# 8-Bit_Instruction_Register_Part_3.net
KiCad netlist of a schematic drawn in EAGLE
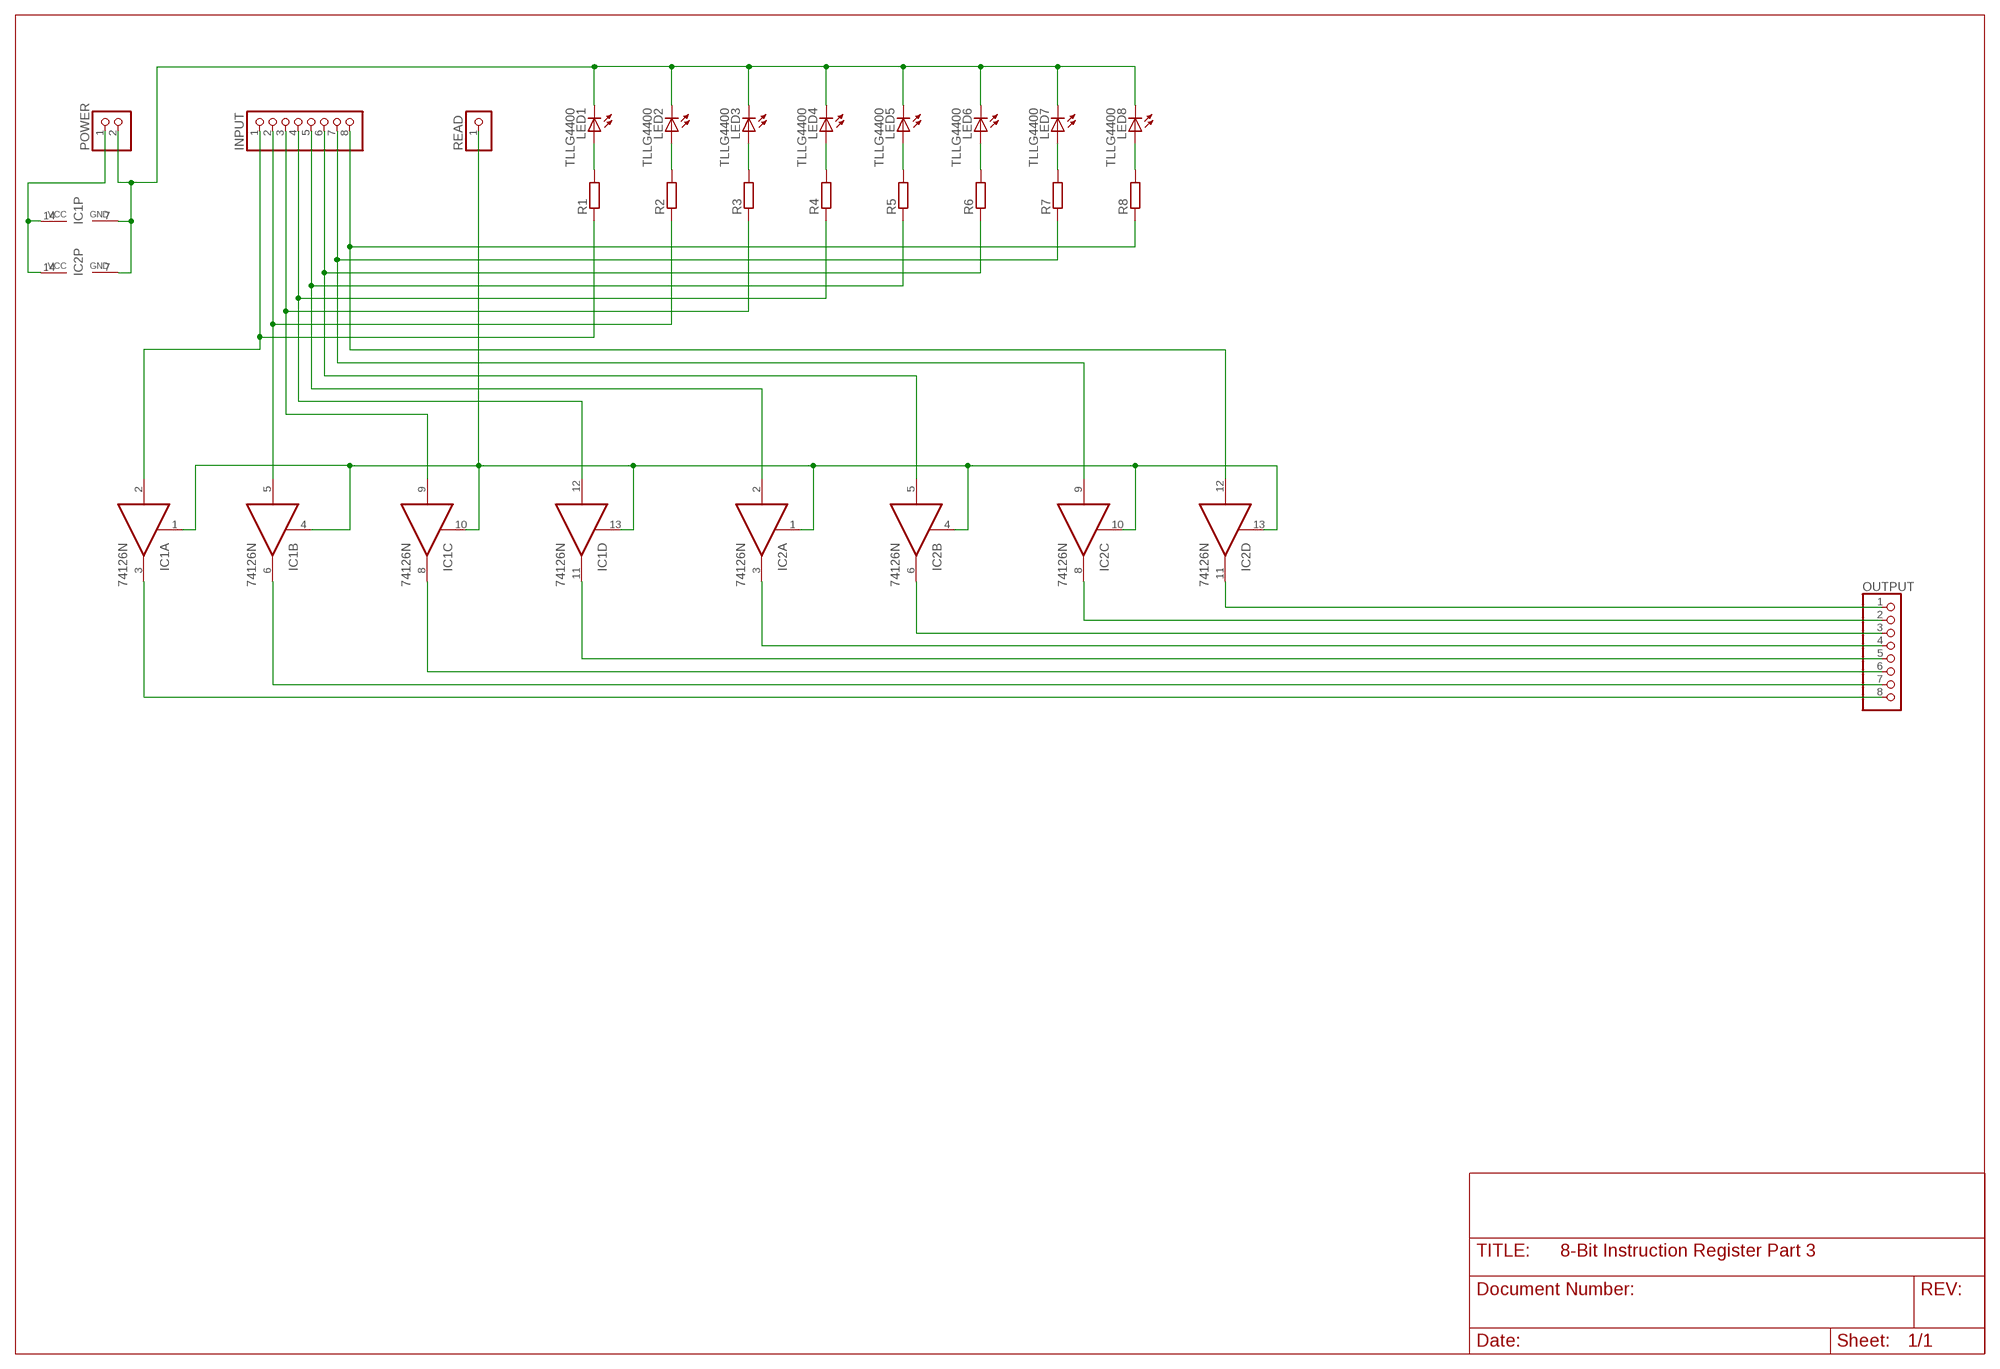
[diagram p0: schematic, sheet 1]

(export (version "E")
  (design (tool "Eeschema 10.0.6"))
  (components
    (comp (ref "IC1")
      (value "74126N")
      (footprint "eagle-import:DIL14")
      (libsource (lib "eagle-import") (part "74126N"))
    )
    (comp (ref "IC2")
      (value "74126N")
      (footprint "eagle-import:DIL14")
      (libsource (lib "eagle-import") (part "74126N"))
    )
    (comp (ref "INPUT")
      (value "PINHD-1X8")
      (footprint "eagle-import:1X08")
      (libsource (lib "eagle-import") (part "PINHD-1X8"))
    )
    (comp (ref "LED1")
      (value "TLLG4400")
      (footprint "eagle-import:LED3MM")
      (fields (field (name "MF") "VISHAY SEMICONDUCTOR"))
      (libsource (lib "eagle-import") (part "TLLG4400"))
    )
    (comp (ref "LED2")
      (value "TLLG4400")
      (footprint "eagle-import:LED3MM")
      (fields (field (name "MF") "VISHAY SEMICONDUCTOR"))
      (libsource (lib "eagle-import") (part "TLLG4400"))
    )
    (comp (ref "LED3")
      (value "TLLG4400")
      (footprint "eagle-import:LED3MM")
      (fields (field (name "MF") "VISHAY SEMICONDUCTOR"))
      (libsource (lib "eagle-import") (part "TLLG4400"))
    )
    (comp (ref "LED4")
      (value "TLLG4400")
      (footprint "eagle-import:LED3MM")
      (fields (field (name "MF") "VISHAY SEMICONDUCTOR"))
      (libsource (lib "eagle-import") (part "TLLG4400"))
    )
    (comp (ref "LED5")
      (value "TLLG4400")
      (footprint "eagle-import:LED3MM")
      (fields (field (name "MF") "VISHAY SEMICONDUCTOR"))
      (libsource (lib "eagle-import") (part "TLLG4400"))
    )
    (comp (ref "LED6")
      (value "TLLG4400")
      (footprint "eagle-import:LED3MM")
      (fields (field (name "MF") "VISHAY SEMICONDUCTOR"))
      (libsource (lib "eagle-import") (part "TLLG4400"))
    )
    (comp (ref "LED7")
      (value "TLLG4400")
      (footprint "eagle-import:LED3MM")
      (fields (field (name "MF") "VISHAY SEMICONDUCTOR"))
      (libsource (lib "eagle-import") (part "TLLG4400"))
    )
    (comp (ref "LED8")
      (value "TLLG4400")
      (footprint "eagle-import:LED3MM")
      (fields (field (name "MF") "VISHAY SEMICONDUCTOR"))
      (libsource (lib "eagle-import") (part "TLLG4400"))
    )
    (comp (ref "OUTPUT")
      (value "PINHD-1X8")
      (footprint "eagle-import:1X08")
      (libsource (lib "eagle-import") (part "PINHD-1X8"))
    )
    (comp (ref "POWER")
      (value "PINHD-1X2")
      (footprint "eagle-import:1X02")
      (libsource (lib "eagle-import") (part "PINHD-1X2"))
    )
    (comp (ref "R1")
      (value "R-EU_0207/7")
      (footprint "eagle-import:0207_7")
      (libsource (lib "eagle-import") (part "R-EU_0207/7"))
    )
    (comp (ref "R2")
      (value "R-EU_0207/7")
      (footprint "eagle-import:0207_7")
      (libsource (lib "eagle-import") (part "R-EU_0207/7"))
    )
    (comp (ref "R3")
      (value "R-EU_0207/7")
      (footprint "eagle-import:0207_7")
      (libsource (lib "eagle-import") (part "R-EU_0207/7"))
    )
    (comp (ref "R4")
      (value "R-EU_0207/7")
      (footprint "eagle-import:0207_7")
      (libsource (lib "eagle-import") (part "R-EU_0207/7"))
    )
    (comp (ref "R5")
      (value "R-EU_0207/7")
      (footprint "eagle-import:0207_7")
      (libsource (lib "eagle-import") (part "R-EU_0207/7"))
    )
    (comp (ref "R6")
      (value "R-EU_0207/7")
      (footprint "eagle-import:0207_7")
      (libsource (lib "eagle-import") (part "R-EU_0207/7"))
    )
    (comp (ref "R7")
      (value "R-EU_0207/7")
      (footprint "eagle-import:0207_7")
      (libsource (lib "eagle-import") (part "R-EU_0207/7"))
    )
    (comp (ref "R8")
      (value "R-EU_0207/7")
      (footprint "eagle-import:0207_7")
      (libsource (lib "eagle-import") (part "R-EU_0207/7"))
    )
    (comp (ref "READ")
      (value "PINHD-1X1")
      (footprint "eagle-import:1X01")
      (libsource (lib "eagle-import") (part "PINHD-1X1"))
    )
  )
  (nets
    (net (code "1") (name "Net-(IC1A-I)") (class "Default")
      (node (ref "IC1") (pin "2") (pinfunction "I_2") (pintype "input"))
      (node (ref "INPUT") (pin "1") (pinfunction "1_1") (pintype "passive"))
      (node (ref "R1") (pin "1") (pinfunction "1_1") (pintype "passive"))
    )
    (net (code "2") (name "Net-(IC1A-O)") (class "Default")
      (node (ref "IC1") (pin "3") (pinfunction "O_3") (pintype "output"))
      (node (ref "OUTPUT") (pin "8") (pinfunction "8_8") (pintype "passive"))
    )
    (net (code "3") (name "Net-(IC1A-OE)") (class "Default")
      (node (ref "IC1") (pin "1") (pinfunction "OE_1") (pintype "input"))
      (node (ref "IC1") (pin "10") (pinfunction "OE_10") (pintype "input"))
      (node (ref "IC1") (pin "13") (pinfunction "OE_13") (pintype "input"))
      (node (ref "IC1") (pin "4") (pinfunction "OE_4") (pintype "input"))
      (node (ref "IC2") (pin "1") (pinfunction "OE_1") (pintype "input"))
      (node (ref "IC2") (pin "10") (pinfunction "OE_10") (pintype "input"))
      (node (ref "IC2") (pin "13") (pinfunction "OE_13") (pintype "input"))
      (node (ref "IC2") (pin "4") (pinfunction "OE_4") (pintype "input"))
      (node (ref "READ") (pin "1") (pinfunction "1_1") (pintype "passive"))
    )
    (net (code "4") (name "Net-(IC1B-I)") (class "Default")
      (node (ref "IC1") (pin "5") (pinfunction "I_5") (pintype "input"))
      (node (ref "INPUT") (pin "2") (pinfunction "2_2") (pintype "passive"))
      (node (ref "R2") (pin "1") (pinfunction "1_1") (pintype "passive"))
    )
    (net (code "5") (name "Net-(IC1B-O)") (class "Default")
      (node (ref "IC1") (pin "6") (pinfunction "O_6") (pintype "output"))
      (node (ref "OUTPUT") (pin "7") (pinfunction "7_7") (pintype "passive"))
    )
    (net (code "6") (name "Net-(IC1C-I)") (class "Default")
      (node (ref "IC1") (pin "9") (pinfunction "I_9") (pintype "input"))
      (node (ref "INPUT") (pin "3") (pinfunction "3_3") (pintype "passive"))
      (node (ref "R3") (pin "1") (pinfunction "1_1") (pintype "passive"))
    )
    (net (code "7") (name "Net-(IC1C-O)") (class "Default")
      (node (ref "IC1") (pin "8") (pinfunction "O_8") (pintype "output"))
      (node (ref "OUTPUT") (pin "6") (pinfunction "6_6") (pintype "passive"))
    )
    (net (code "8") (name "Net-(IC1D-I)") (class "Default")
      (node (ref "IC1") (pin "12") (pinfunction "I_12") (pintype "input"))
      (node (ref "INPUT") (pin "4") (pinfunction "4_4") (pintype "passive"))
      (node (ref "R4") (pin "1") (pinfunction "1_1") (pintype "passive"))
    )
    (net (code "9") (name "Net-(IC1D-O)") (class "Default")
      (node (ref "IC1") (pin "11") (pinfunction "O_11") (pintype "output"))
      (node (ref "OUTPUT") (pin "5") (pinfunction "5_5") (pintype "passive"))
    )
    (net (code "10") (name "Net-(IC1E-GND)") (class "Default")
      (node (ref "IC1") (pin "7") (pinfunction "GND_7") (pintype "power_in"))
      (node (ref "IC2") (pin "7") (pinfunction "GND_7") (pintype "power_in"))
      (node (ref "LED1") (pin "K") (pinfunction "C_K") (pintype "passive"))
      (node (ref "LED2") (pin "K") (pinfunction "C_K") (pintype "passive"))
      (node (ref "LED3") (pin "K") (pinfunction "C_K") (pintype "passive"))
      (node (ref "LED4") (pin "K") (pinfunction "C_K") (pintype "passive"))
      (node (ref "LED5") (pin "K") (pinfunction "C_K") (pintype "passive"))
      (node (ref "LED6") (pin "K") (pinfunction "C_K") (pintype "passive"))
      (node (ref "LED7") (pin "K") (pinfunction "C_K") (pintype "passive"))
      (node (ref "LED8") (pin "K") (pinfunction "C_K") (pintype "passive"))
      (node (ref "POWER") (pin "2") (pinfunction "2_2") (pintype "passive"))
    )
    (net (code "11") (name "Net-(IC1E-VCC)") (class "Default")
      (node (ref "IC1") (pin "14") (pinfunction "VCC_14") (pintype "power_in"))
      (node (ref "IC2") (pin "14") (pinfunction "VCC_14") (pintype "power_in"))
      (node (ref "POWER") (pin "1") (pinfunction "1_1") (pintype "passive"))
    )
    (net (code "12") (name "Net-(IC2A-I)") (class "Default")
      (node (ref "IC2") (pin "2") (pinfunction "I_2") (pintype "input"))
      (node (ref "INPUT") (pin "5") (pinfunction "5_5") (pintype "passive"))
      (node (ref "R5") (pin "1") (pinfunction "1_1") (pintype "passive"))
    )
    (net (code "13") (name "Net-(IC2A-O)") (class "Default")
      (node (ref "IC2") (pin "3") (pinfunction "O_3") (pintype "output"))
      (node (ref "OUTPUT") (pin "4") (pinfunction "4_4") (pintype "passive"))
    )
    (net (code "14") (name "Net-(IC2B-I)") (class "Default")
      (node (ref "IC2") (pin "5") (pinfunction "I_5") (pintype "input"))
      (node (ref "INPUT") (pin "6") (pinfunction "6_6") (pintype "passive"))
      (node (ref "R6") (pin "1") (pinfunction "1_1") (pintype "passive"))
    )
    (net (code "15") (name "Net-(IC2B-O)") (class "Default")
      (node (ref "IC2") (pin "6") (pinfunction "O_6") (pintype "output"))
      (node (ref "OUTPUT") (pin "3") (pinfunction "3_3") (pintype "passive"))
    )
    (net (code "16") (name "Net-(IC2C-I)") (class "Default")
      (node (ref "IC2") (pin "9") (pinfunction "I_9") (pintype "input"))
      (node (ref "INPUT") (pin "7") (pinfunction "7_7") (pintype "passive"))
      (node (ref "R7") (pin "1") (pinfunction "1_1") (pintype "passive"))
    )
    (net (code "17") (name "Net-(IC2C-O)") (class "Default")
      (node (ref "IC2") (pin "8") (pinfunction "O_8") (pintype "output"))
      (node (ref "OUTPUT") (pin "2") (pinfunction "2_2") (pintype "passive"))
    )
    (net (code "18") (name "Net-(IC2D-I)") (class "Default")
      (node (ref "IC2") (pin "12") (pinfunction "I_12") (pintype "input"))
      (node (ref "INPUT") (pin "8") (pinfunction "8_8") (pintype "passive"))
      (node (ref "R8") (pin "1") (pinfunction "1_1") (pintype "passive"))
    )
    (net (code "19") (name "Net-(IC2D-O)") (class "Default")
      (node (ref "IC2") (pin "11") (pinfunction "O_11") (pintype "output"))
      (node (ref "OUTPUT") (pin "1") (pinfunction "1_1") (pintype "passive"))
    )
    (net (code "20") (name "Net-(LED1-PadA)") (class "Default")
      (node (ref "LED1") (pin "A") (pinfunction "A_A") (pintype "passive"))
      (node (ref "R1") (pin "2") (pinfunction "2_2") (pintype "passive"))
    )
    (net (code "21") (name "Net-(LED2-PadA)") (class "Default")
      (node (ref "LED2") (pin "A") (pinfunction "A_A") (pintype "passive"))
      (node (ref "R2") (pin "2") (pinfunction "2_2") (pintype "passive"))
    )
    (net (code "22") (name "Net-(LED3-PadA)") (class "Default")
      (node (ref "LED3") (pin "A") (pinfunction "A_A") (pintype "passive"))
      (node (ref "R3") (pin "2") (pinfunction "2_2") (pintype "passive"))
    )
    (net (code "23") (name "Net-(LED4-PadA)") (class "Default")
      (node (ref "LED4") (pin "A") (pinfunction "A_A") (pintype "passive"))
      (node (ref "R4") (pin "2") (pinfunction "2_2") (pintype "passive"))
    )
    (net (code "24") (name "Net-(LED5-PadA)") (class "Default")
      (node (ref "LED5") (pin "A") (pinfunction "A_A") (pintype "passive"))
      (node (ref "R5") (pin "2") (pinfunction "2_2") (pintype "passive"))
    )
    (net (code "25") (name "Net-(LED6-PadA)") (class "Default")
      (node (ref "LED6") (pin "A") (pinfunction "A_A") (pintype "passive"))
      (node (ref "R6") (pin "2") (pinfunction "2_2") (pintype "passive"))
    )
    (net (code "26") (name "Net-(LED7-PadA)") (class "Default")
      (node (ref "LED7") (pin "A") (pinfunction "A_A") (pintype "passive"))
      (node (ref "R7") (pin "2") (pinfunction "2_2") (pintype "passive"))
    )
    (net (code "27") (name "Net-(LED8-PadA)") (class "Default")
      (node (ref "LED8") (pin "A") (pinfunction "A_A") (pintype "passive"))
      (node (ref "R8") (pin "2") (pinfunction "2_2") (pintype "passive"))
    )
  )
)
